# untitled.net
KiCad netlist of a schematic drawn in EAGLE
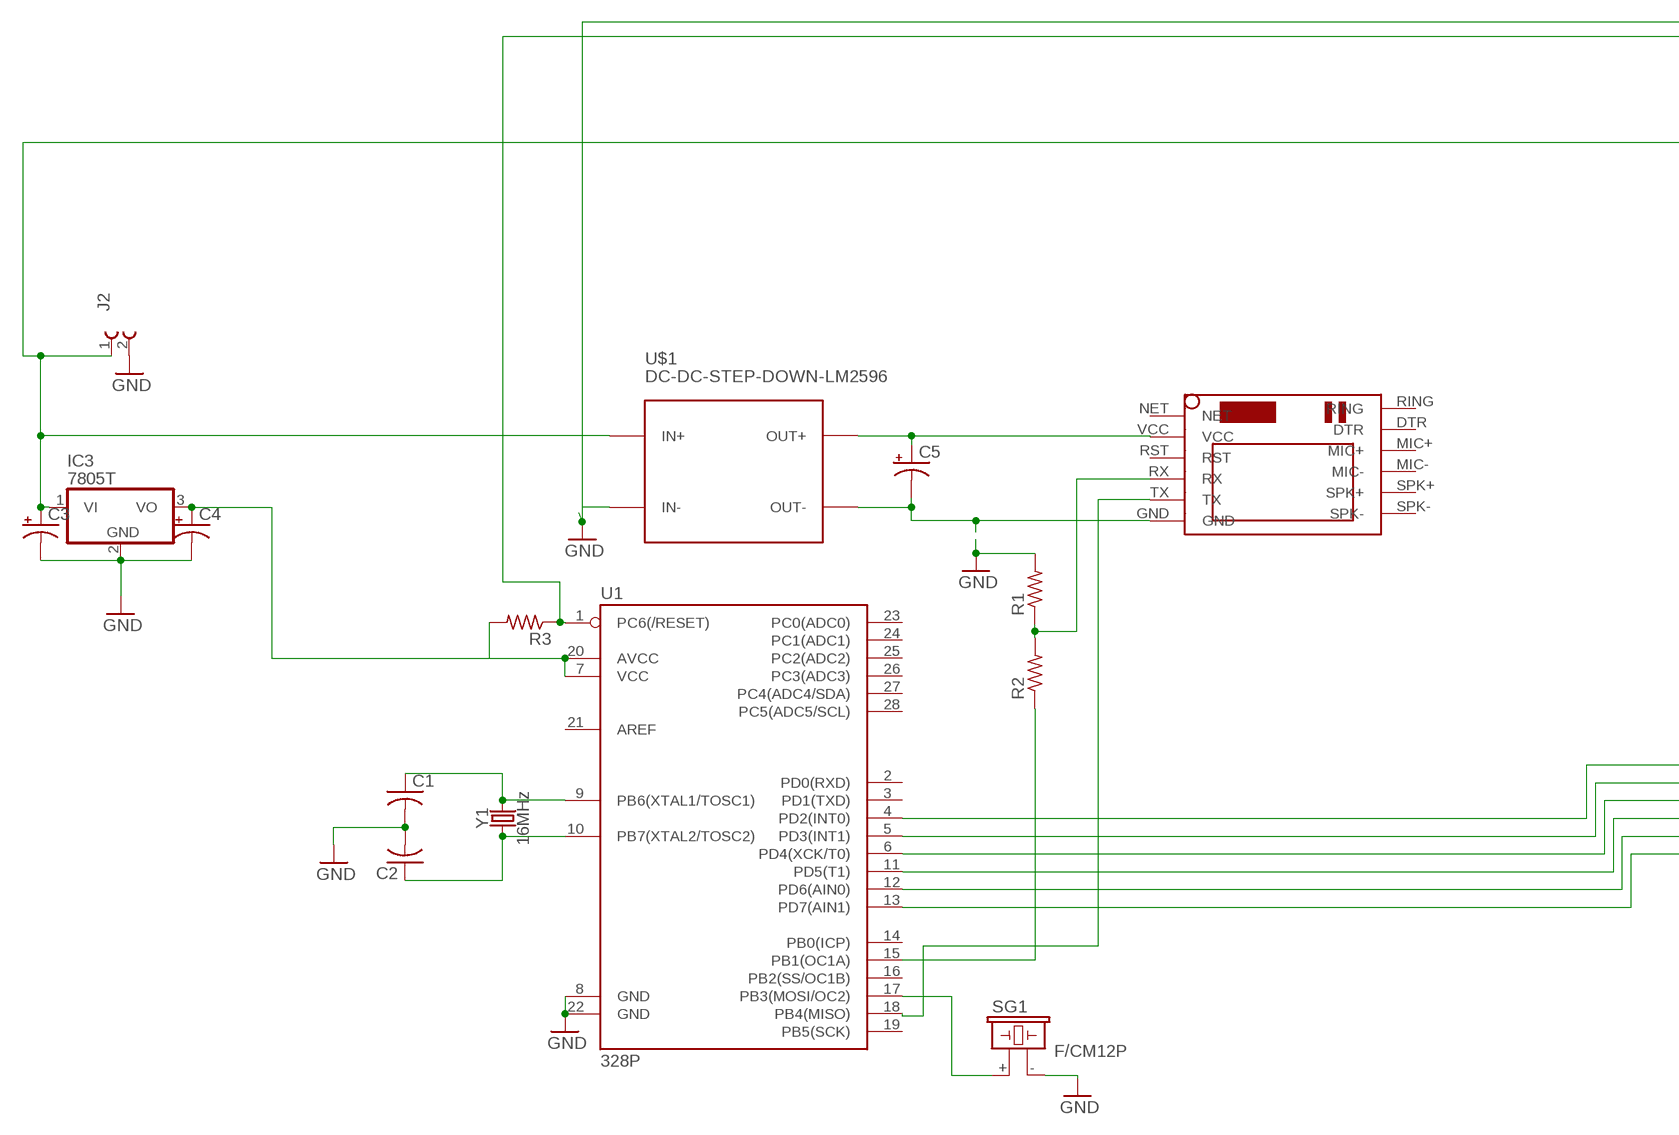
[diagram p0: schematic, sheet 1, part 1 of 2]
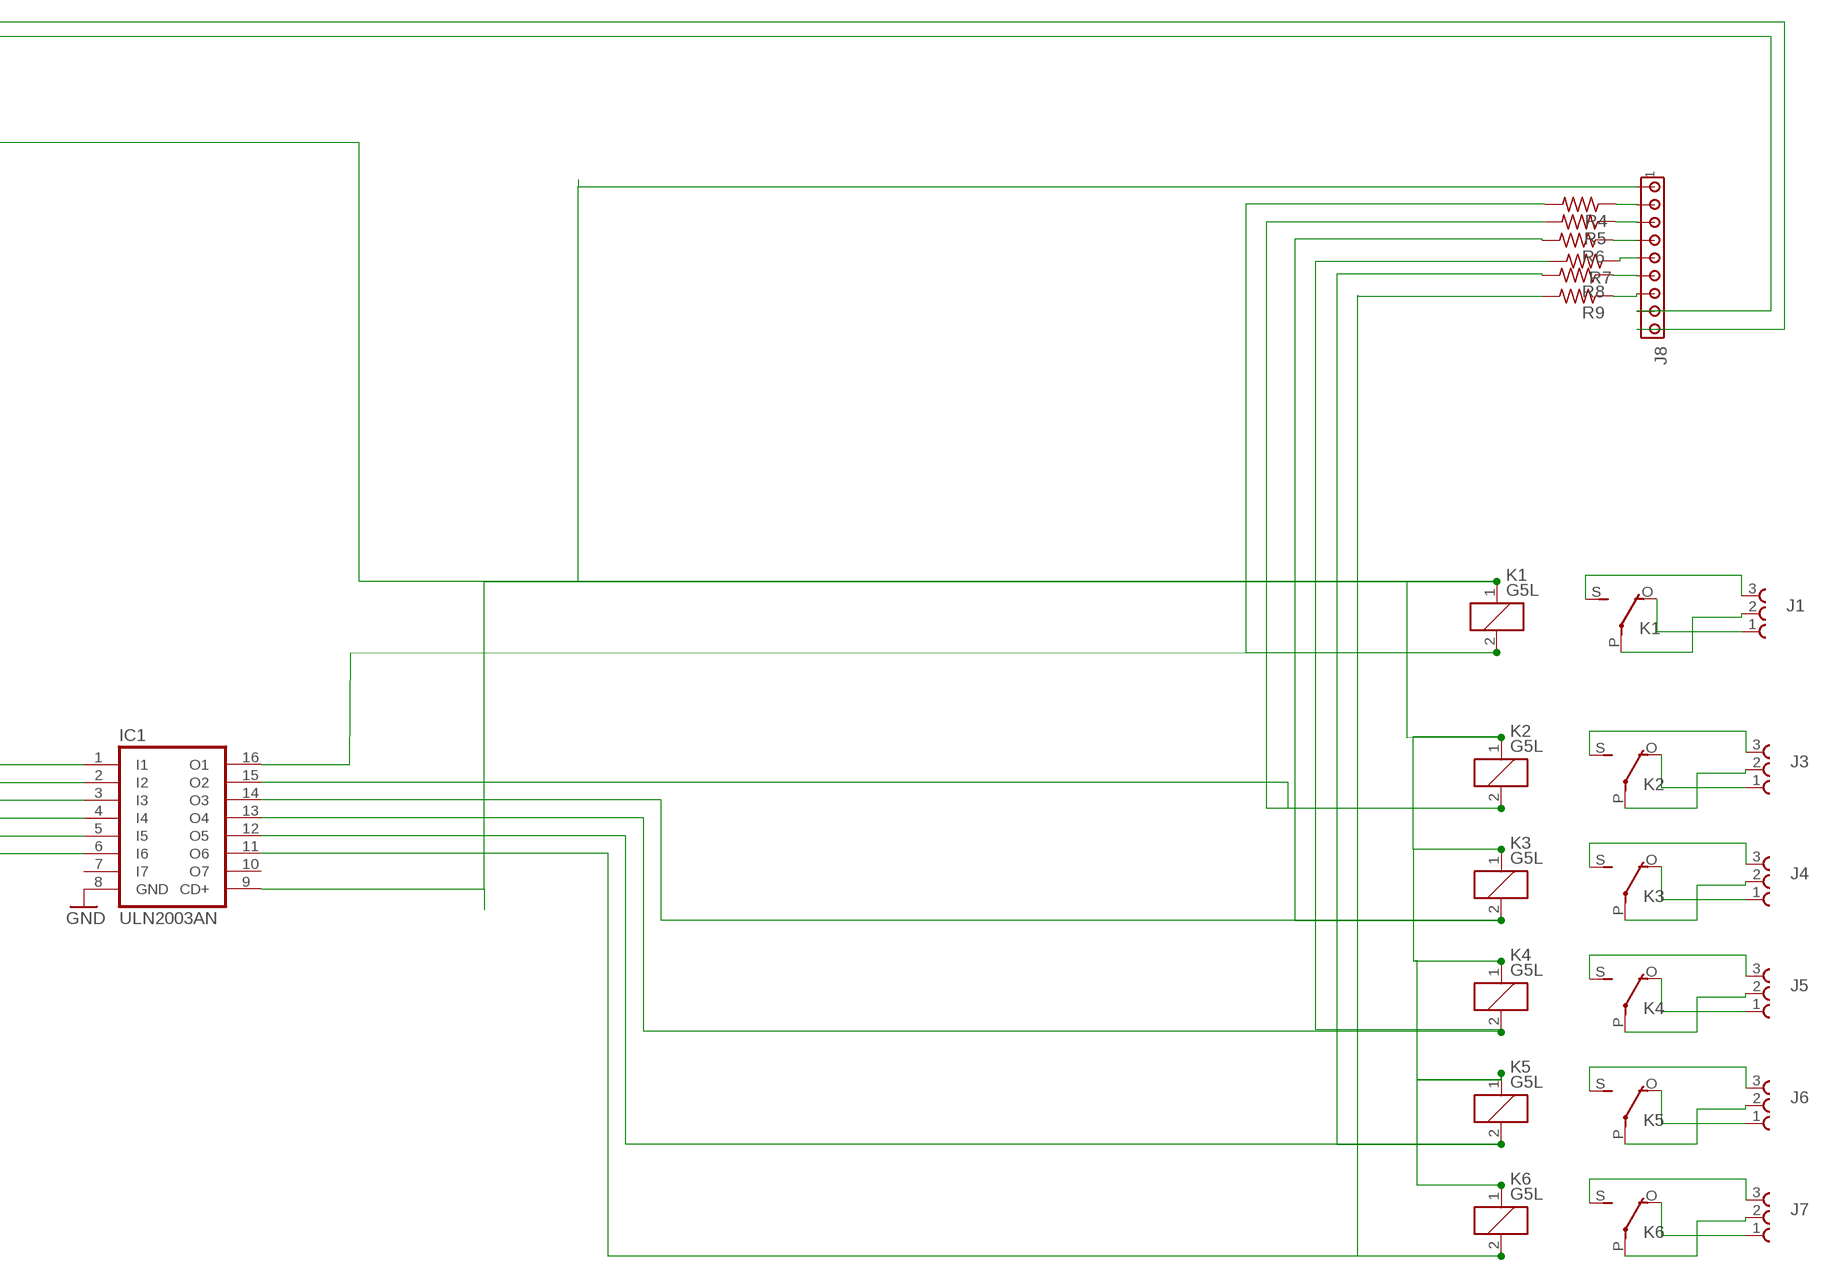
[diagram p1: schematic, sheet 1, part 2 of 2]

(export (version "E")
  (design (tool "Eeschema 10.0.6"))
  (components
    (comp (ref "C1")
      (value "C-US025-024X044")
      (footprint "eagle-import:C025-024X044")
      (libsource (lib "eagle-import") (part "C-US025-024X044"))
    )
    (comp (ref "C2")
      (value "C-US025-024X044")
      (footprint "eagle-import:C025-024X044")
      (libsource (lib "eagle-import") (part "C-US025-024X044"))
    )
    (comp (ref "C3")
      (value "CPOL-USE2.5-5")
      (footprint "eagle-import:E2,5-5")
      (libsource (lib "eagle-import") (part "CPOL-USE2.5-5"))
    )
    (comp (ref "C4")
      (value "CPOL-USE2.5-5")
      (footprint "eagle-import:E2,5-5")
      (libsource (lib "eagle-import") (part "CPOL-USE2.5-5"))
    )
    (comp (ref "C5")
      (value "CAPACITOR-PE5-8.5")
      (footprint "eagle-import:E5-8,5")
      (libsource (lib "eagle-import") (part "CAPACITOR-PE5-8.5"))
    )
    (comp (ref "IC1")
      (value "ULN2003AN")
      (footprint "eagle-import:DIL16")
      (libsource (lib "eagle-import") (part "ULN2003AN"))
    )
    (comp (ref "IC3")
      (value "7805T")
      (footprint "eagle-import:TO220H")
      (libsource (lib "eagle-import") (part "78T05"))
    )
    (comp (ref "J1")
      (value "691216700003")
      (footprint "eagle-import:691216700003")
      (libsource (lib "eagle-import") (part "691216700003"))
    )
    (comp (ref "J2")
      (value "691217910002")
      (footprint "eagle-import:691217910002")
      (libsource (lib "eagle-import") (part "691217910002"))
    )
    (comp (ref "J3")
      (value "691216700003")
      (footprint "eagle-import:691216700003")
      (libsource (lib "eagle-import") (part "691216700003"))
    )
    (comp (ref "J4")
      (value "691216700003")
      (footprint "eagle-import:691216700003")
      (libsource (lib "eagle-import") (part "691216700003"))
    )
    (comp (ref "J5")
      (value "691216700003")
      (footprint "eagle-import:691216700003")
      (libsource (lib "eagle-import") (part "691216700003"))
    )
    (comp (ref "J6")
      (value "691216700003")
      (footprint "eagle-import:691216700003")
      (libsource (lib "eagle-import") (part "691216700003"))
    )
    (comp (ref "J7")
      (value "691216700003")
      (footprint "eagle-import:691216700003")
      (libsource (lib "eagle-import") (part "691216700003"))
    )
    (comp (ref "J8")
      (value "MTA09-100")
      (footprint "eagle-import:10X09MTA")
      (libsource (lib "eagle-import") (part "MTA09-100"))
    )
    (comp (ref "K1")
      (value "G5L")
      (footprint "eagle-import:G5LE")
      (libsource (lib "eagle-import") (part "G5L"))
    )
    (comp (ref "K2")
      (value "G5L")
      (footprint "eagle-import:G5LE")
      (libsource (lib "eagle-import") (part "G5L"))
    )
    (comp (ref "K3")
      (value "G5L")
      (footprint "eagle-import:G5LE")
      (libsource (lib "eagle-import") (part "G5L"))
    )
    (comp (ref "K4")
      (value "G5L")
      (footprint "eagle-import:G5LE")
      (libsource (lib "eagle-import") (part "G5L"))
    )
    (comp (ref "K5")
      (value "G5L")
      (footprint "eagle-import:G5LE")
      (libsource (lib "eagle-import") (part "G5L"))
    )
    (comp (ref "K6")
      (value "G5L")
      (footprint "eagle-import:G5LE")
      (libsource (lib "eagle-import") (part "G5L"))
    )
    (comp (ref "R1")
      (value "R-US_0204/7")
      (footprint "eagle-import:0204_7")
      (libsource (lib "eagle-import") (part "R-US_0204/7"))
    )
    (comp (ref "R2")
      (value "R-US_0204/7")
      (footprint "eagle-import:0204_7")
      (libsource (lib "eagle-import") (part "R-US_0204/7"))
    )
    (comp (ref "R3")
      (value "R-US_0204/7")
      (footprint "eagle-import:0204_7")
      (libsource (lib "eagle-import") (part "R-US_0204/7"))
    )
    (comp (ref "R4")
      (value "R-US_0204/7")
      (footprint "eagle-import:0204_7")
      (libsource (lib "eagle-import") (part "R-US_0204/7"))
    )
    (comp (ref "R5")
      (value "R-US_0204/7")
      (footprint "eagle-import:0204_7")
      (libsource (lib "eagle-import") (part "R-US_0204/7"))
    )
    (comp (ref "R6")
      (value "R-US_0204/7")
      (footprint "eagle-import:0204_7")
      (libsource (lib "eagle-import") (part "R-US_0204/7"))
    )
    (comp (ref "R7")
      (value "R-US_0204/7")
      (footprint "eagle-import:0204_7")
      (libsource (lib "eagle-import") (part "R-US_0204/7"))
    )
    (comp (ref "R8")
      (value "R-US_0204/7")
      (footprint "eagle-import:0204_7")
      (libsource (lib "eagle-import") (part "R-US_0204/7"))
    )
    (comp (ref "R9")
      (value "R-US_0204/7")
      (footprint "eagle-import:0204_7")
      (libsource (lib "eagle-import") (part "R-US_0204/7"))
    )
    (comp (ref "SG1")
      (value "F/CM12P")
      (footprint "eagle-import:F_CM12P")
      (libsource (lib "eagle-import") (part "F/CM12P"))
    )
    (comp (ref "U$1")
      (value "DC-DC-STEP-DOWN-LM2596")
      (footprint "eagle-import:DC-DC-STEP-DOWN-LM2596")
      (libsource (lib "eagle-import") (part "DC-DC-STEP-DOWN-LM2596"))
    )
    (comp (ref "U$2")
      (value "SIM800LMODULE")
      (footprint "eagle-import:SIM800LMODULE")
      (libsource (lib "eagle-import") (part "SIM800LMODULE"))
    )
    (comp (ref "U1")
      (value "328P")
      (footprint "eagle-import:DIP28")
      (libsource (lib "eagle-import") (part "ATMEGA328P_PDIP"))
    )
    (comp (ref "Y1")
      (value "16MHz")
      (footprint "eagle-import:HC49US")
      (libsource (lib "eagle-import") (part "CRYSTAL-16MHZPTH-HC49US"))
    )
  )
  (nets
    (net (code "1") (name "GND") (class "Default")
      (node (ref "C1") (pin "2") (pinfunction "2_2") (pintype "passive"))
      (node (ref "C2") (pin "2") (pinfunction "2_2") (pintype "passive"))
      (node (ref "C3") (pin "-") (pinfunction "-_-") (pintype "passive"))
      (node (ref "C4") (pin "-") (pinfunction "-_-") (pintype "passive"))
      (node (ref "C5") (pin "-") (pinfunction "-_-") (pintype "passive"))
      (node (ref "IC1") (pin "8") (pinfunction "GND_8") (pintype "power_in"))
      (node (ref "IC3") (pin "2") (pinfunction "GND_2") (pintype "passive"))
      (node (ref "J2") (pin "2") (pinfunction "2_2") (pintype "passive"))
      (node (ref "J8") (pin "9") (pinfunction "9_9") (pintype "passive"))
      (node (ref "R1") (pin "2") (pinfunction "2_2") (pintype "passive"))
      (node (ref "SG1") (pin "-") (pinfunction "2_-") (pintype "passive"))
      (node (ref "U$1") (pin "IN-") (pinfunction "IN-_IN-") (pintype "bidirectional"))
      (node (ref "U$1") (pin "OUT-") (pinfunction "OUT-_OUT-") (pintype "bidirectional"))
      (node (ref "U$2") (pin "GND") (pinfunction "GND_GND") (pintype "bidirectional"))
      (node (ref "U1") (pin "22") (pinfunction "GND_22") (pintype "bidirectional"))
      (node (ref "U1") (pin "8") (pinfunction "GND_8") (pintype "bidirectional"))
    )
    (net (code "2") (name "Net-(C5-Pad+)") (class "Default")
      (node (ref "C5") (pin "+") (pinfunction "+_+") (pintype "passive"))
      (node (ref "U$1") (pin "OUT+") (pinfunction "OUT+_OUT+") (pintype "bidirectional"))
      (node (ref "U$2") (pin "VCC") (pinfunction "VCC_VCC") (pintype "bidirectional"))
    )
    (net (code "3") (name "Net-(IC1-CD+)") (class "Default")
      (node (ref "C3") (pin "+") (pinfunction "+_+") (pintype "passive"))
      (node (ref "IC1") (pin "9") (pinfunction "CD+_9") (pintype "passive"))
      (node (ref "IC3") (pin "1") (pinfunction "VI_1") (pintype "input"))
      (node (ref "J2") (pin "1") (pinfunction "1_1") (pintype "passive"))
      (node (ref "J8") (pin "1") (pinfunction "1_1") (pintype "passive"))
      (node (ref "K1") (pin "1") (pinfunction "1_1") (pintype "passive"))
      (node (ref "K2") (pin "1") (pinfunction "1_1") (pintype "passive"))
      (node (ref "K3") (pin "1") (pinfunction "1_1") (pintype "passive"))
      (node (ref "K4") (pin "1") (pinfunction "1_1") (pintype "passive"))
      (node (ref "K5") (pin "1") (pinfunction "1_1") (pintype "passive"))
      (node (ref "K6") (pin "1") (pinfunction "1_1") (pintype "passive"))
      (node (ref "U$1") (pin "IN+") (pinfunction "IN+_IN+") (pintype "bidirectional"))
    )
    (net (code "4") (name "Net-(IC1-I1)") (class "Default")
      (node (ref "IC1") (pin "1") (pinfunction "I1_1") (pintype "input"))
      (node (ref "U1") (pin "4") (pinfunction "PD2(INT0)_4") (pintype "bidirectional"))
    )
    (net (code "5") (name "Net-(IC1-I2)") (class "Default")
      (node (ref "IC1") (pin "2") (pinfunction "I2_2") (pintype "input"))
      (node (ref "U1") (pin "5") (pinfunction "PD3(INT1)_5") (pintype "bidirectional"))
    )
    (net (code "6") (name "Net-(IC1-I3)") (class "Default")
      (node (ref "IC1") (pin "3") (pinfunction "I3_3") (pintype "input"))
      (node (ref "U1") (pin "6") (pinfunction "PD4(XCK/T0)_6") (pintype "bidirectional"))
    )
    (net (code "7") (name "Net-(IC1-I4)") (class "Default")
      (node (ref "IC1") (pin "4") (pinfunction "I4_4") (pintype "input"))
      (node (ref "U1") (pin "11") (pinfunction "PD5(T1)_11") (pintype "bidirectional"))
    )
    (net (code "8") (name "Net-(IC1-I5)") (class "Default")
      (node (ref "IC1") (pin "5") (pinfunction "I5_5") (pintype "input"))
      (node (ref "U1") (pin "12") (pinfunction "PD6(AIN0)_12") (pintype "bidirectional"))
    )
    (net (code "9") (name "Net-(IC1-I6)") (class "Default")
      (node (ref "IC1") (pin "6") (pinfunction "I6_6") (pintype "input"))
      (node (ref "U1") (pin "13") (pinfunction "PD7(AIN1)_13") (pintype "bidirectional"))
    )
    (net (code "10") (name "Net-(IC1-O1)") (class "Default")
      (node (ref "IC1") (pin "16") (pinfunction "O1_16") (pintype "open_collector"))
      (node (ref "K1") (pin "2") (pinfunction "2_2") (pintype "passive"))
      (node (ref "R4") (pin "2") (pinfunction "2_2") (pintype "passive"))
    )
    (net (code "11") (name "Net-(IC1-O2)") (class "Default")
      (node (ref "IC1") (pin "15") (pinfunction "O2_15") (pintype "open_collector"))
      (node (ref "K2") (pin "2") (pinfunction "2_2") (pintype "passive"))
      (node (ref "R5") (pin "2") (pinfunction "2_2") (pintype "passive"))
    )
    (net (code "12") (name "Net-(IC1-O3)") (class "Default")
      (node (ref "IC1") (pin "14") (pinfunction "O3_14") (pintype "open_collector"))
      (node (ref "K3") (pin "2") (pinfunction "2_2") (pintype "passive"))
      (node (ref "R6") (pin "2") (pinfunction "2_2") (pintype "passive"))
    )
    (net (code "13") (name "Net-(IC1-O4)") (class "Default")
      (node (ref "IC1") (pin "13") (pinfunction "O4_13") (pintype "open_collector"))
      (node (ref "K4") (pin "2") (pinfunction "2_2") (pintype "passive"))
      (node (ref "R7") (pin "2") (pinfunction "2_2") (pintype "passive"))
    )
    (net (code "14") (name "Net-(IC1-O5)") (class "Default")
      (node (ref "IC1") (pin "12") (pinfunction "O5_12") (pintype "open_collector"))
      (node (ref "K5") (pin "2") (pinfunction "2_2") (pintype "passive"))
      (node (ref "R8") (pin "2") (pinfunction "2_2") (pintype "passive"))
    )
    (net (code "15") (name "Net-(IC1-O6)") (class "Default")
      (node (ref "IC1") (pin "11") (pinfunction "O6_11") (pintype "open_collector"))
      (node (ref "K6") (pin "2") (pinfunction "2_2") (pintype "passive"))
      (node (ref "R9") (pin "2") (pinfunction "2_2") (pintype "passive"))
    )
    (net (code "16") (name "Net-(IC3-VO)") (class "Default")
      (node (ref "C4") (pin "+") (pinfunction "+_+") (pintype "passive"))
      (node (ref "IC3") (pin "3") (pinfunction "VO_3") (pintype "passive"))
      (node (ref "R3") (pin "2") (pinfunction "2_2") (pintype "passive"))
      (node (ref "U1") (pin "20") (pinfunction "AVCC_20") (pintype "bidirectional"))
      (node (ref "U1") (pin "7") (pinfunction "VCC_7") (pintype "bidirectional"))
    )
    (net (code "17") (name "Net-(J1-1)") (class "Default")
      (node (ref "J1") (pin "3") (pinfunction "1_3") (pintype "passive"))
      (node (ref "K1") (pin "S") (pinfunction "S_S") (pintype "passive"))
    )
    (net (code "18") (name "Net-(J1-3)") (class "Default")
      (node (ref "J1") (pin "1") (pinfunction "3_1") (pintype "passive"))
      (node (ref "K1") (pin "O") (pinfunction "O_O") (pintype "passive"))
    )
    (net (code "19") (name "Net-(J1-Pad2)") (class "Default")
      (node (ref "J1") (pin "2") (pinfunction "2_2") (pintype "passive"))
      (node (ref "K1") (pin "P") (pinfunction "P_P") (pintype "passive"))
    )
    (net (code "20") (name "Net-(J3-1)") (class "Default")
      (node (ref "J3") (pin "3") (pinfunction "1_3") (pintype "passive"))
      (node (ref "K2") (pin "S") (pinfunction "S_S") (pintype "passive"))
    )
    (net (code "21") (name "Net-(J3-3)") (class "Default")
      (node (ref "J3") (pin "1") (pinfunction "3_1") (pintype "passive"))
      (node (ref "K2") (pin "O") (pinfunction "O_O") (pintype "passive"))
    )
    (net (code "22") (name "Net-(J3-Pad2)") (class "Default")
      (node (ref "J3") (pin "2") (pinfunction "2_2") (pintype "passive"))
      (node (ref "K2") (pin "P") (pinfunction "P_P") (pintype "passive"))
    )
    (net (code "23") (name "Net-(J4-1)") (class "Default")
      (node (ref "J4") (pin "3") (pinfunction "1_3") (pintype "passive"))
      (node (ref "K3") (pin "S") (pinfunction "S_S") (pintype "passive"))
    )
    (net (code "24") (name "Net-(J4-3)") (class "Default")
      (node (ref "J4") (pin "1") (pinfunction "3_1") (pintype "passive"))
      (node (ref "K3") (pin "O") (pinfunction "O_O") (pintype "passive"))
    )
    (net (code "25") (name "Net-(J4-Pad2)") (class "Default")
      (node (ref "J4") (pin "2") (pinfunction "2_2") (pintype "passive"))
      (node (ref "K3") (pin "P") (pinfunction "P_P") (pintype "passive"))
    )
    (net (code "26") (name "Net-(J5-1)") (class "Default")
      (node (ref "J5") (pin "3") (pinfunction "1_3") (pintype "passive"))
      (node (ref "K4") (pin "S") (pinfunction "S_S") (pintype "passive"))
    )
    (net (code "27") (name "Net-(J5-3)") (class "Default")
      (node (ref "J5") (pin "1") (pinfunction "3_1") (pintype "passive"))
      (node (ref "K4") (pin "O") (pinfunction "O_O") (pintype "passive"))
    )
    (net (code "28") (name "Net-(J5-Pad2)") (class "Default")
      (node (ref "J5") (pin "2") (pinfunction "2_2") (pintype "passive"))
      (node (ref "K4") (pin "P") (pinfunction "P_P") (pintype "passive"))
    )
    (net (code "29") (name "Net-(J6-1)") (class "Default")
      (node (ref "J6") (pin "3") (pinfunction "1_3") (pintype "passive"))
      (node (ref "K5") (pin "S") (pinfunction "S_S") (pintype "passive"))
    )
    (net (code "30") (name "Net-(J6-3)") (class "Default")
      (node (ref "J6") (pin "1") (pinfunction "3_1") (pintype "passive"))
      (node (ref "K5") (pin "O") (pinfunction "O_O") (pintype "passive"))
    )
    (net (code "31") (name "Net-(J6-Pad2)") (class "Default")
      (node (ref "J6") (pin "2") (pinfunction "2_2") (pintype "passive"))
      (node (ref "K5") (pin "P") (pinfunction "P_P") (pintype "passive"))
    )
    (net (code "32") (name "Net-(J7-1)") (class "Default")
      (node (ref "J7") (pin "3") (pinfunction "1_3") (pintype "passive"))
      (node (ref "K6") (pin "S") (pinfunction "S_S") (pintype "passive"))
    )
    (net (code "33") (name "Net-(J7-3)") (class "Default")
      (node (ref "J7") (pin "1") (pinfunction "3_1") (pintype "passive"))
      (node (ref "K6") (pin "O") (pinfunction "O_O") (pintype "passive"))
    )
    (net (code "34") (name "Net-(J7-Pad2)") (class "Default")
      (node (ref "J7") (pin "2") (pinfunction "2_2") (pintype "passive"))
      (node (ref "K6") (pin "P") (pinfunction "P_P") (pintype "passive"))
    )
    (net (code "35") (name "Net-(J8-Pad2)") (class "Default")
      (node (ref "J8") (pin "2") (pinfunction "2_2") (pintype "passive"))
      (node (ref "R4") (pin "1") (pinfunction "1_1") (pintype "passive"))
    )
    (net (code "36") (name "Net-(J8-Pad3)") (class "Default")
      (node (ref "J8") (pin "3") (pinfunction "3_3") (pintype "passive"))
      (node (ref "R5") (pin "1") (pinfunction "1_1") (pintype "passive"))
    )
    (net (code "37") (name "Net-(J8-Pad4)") (class "Default")
      (node (ref "J8") (pin "4") (pinfunction "4_4") (pintype "passive"))
      (node (ref "R6") (pin "1") (pinfunction "1_1") (pintype "passive"))
    )
    (net (code "38") (name "Net-(J8-Pad5)") (class "Default")
      (node (ref "J8") (pin "5") (pinfunction "5_5") (pintype "passive"))
      (node (ref "R7") (pin "1") (pinfunction "1_1") (pintype "passive"))
    )
    (net (code "39") (name "Net-(J8-Pad6)") (class "Default")
      (node (ref "J8") (pin "6") (pinfunction "6_6") (pintype "passive"))
      (node (ref "R8") (pin "1") (pinfunction "1_1") (pintype "passive"))
    )
    (net (code "40") (name "Net-(J8-Pad7)") (class "Default")
      (node (ref "J8") (pin "7") (pinfunction "7_7") (pintype "passive"))
      (node (ref "R9") (pin "1") (pinfunction "1_1") (pintype "passive"))
    )
    (net (code "41") (name "Net-(R1-Pad1)") (class "Default")
      (node (ref "R1") (pin "1") (pinfunction "1_1") (pintype "passive"))
      (node (ref "R2") (pin "2") (pinfunction "2_2") (pintype "passive"))
      (node (ref "U$2") (pin "RX") (pinfunction "RX_RX") (pintype "bidirectional"))
    )
    (net (code "42") (name "Net-(SG1-1)") (class "Default")
      (node (ref "SG1") (pin "+") (pinfunction "1_+") (pintype "passive"))
      (node (ref "U1") (pin "17") (pinfunction "PB3(MOSI/OC2)_17") (pintype "bidirectional"))
    )
    (net (code "43") (name "Net-(U1-PB1(OC1A))") (class "Default")
      (node (ref "R2") (pin "1") (pinfunction "1_1") (pintype "passive"))
      (node (ref "U1") (pin "15") (pinfunction "PB1(OC1A)_15") (pintype "bidirectional"))
    )
    (net (code "44") (name "Net-(U1-PB4(MISO))") (class "Default")
      (node (ref "U$2") (pin "TX") (pinfunction "TX_TX") (pintype "bidirectional"))
      (node (ref "U1") (pin "18") (pinfunction "PB4(MISO)_18") (pintype "bidirectional"))
    )
    (net (code "45") (name "Net-(U1-PB6(XTAL1{slash}TOSC1))") (class "Default")
      (node (ref "C1") (pin "1") (pinfunction "1_1") (pintype "passive"))
      (node (ref "U1") (pin "9") (pinfunction "PB6(XTAL1/TOSC1)_9") (pintype "bidirectional"))
      (node (ref "Y1") (pin "2") (pinfunction "2_2") (pintype "passive"))
    )
    (net (code "46") (name "Net-(U1-PB7(XTAL2{slash}TOSC2))") (class "Default")
      (node (ref "C2") (pin "1") (pinfunction "1_1") (pintype "passive"))
      (node (ref "U1") (pin "10") (pinfunction "PB7(XTAL2/TOSC2)_10") (pintype "bidirectional"))
      (node (ref "Y1") (pin "1") (pinfunction "1_1") (pintype "passive"))
    )
    (net (code "47") (name "Net-(U1-PC6({slash}RESET))") (class "Default")
      (node (ref "J8") (pin "8") (pinfunction "8_8") (pintype "passive"))
      (node (ref "R3") (pin "1") (pinfunction "1_1") (pintype "passive"))
      (node (ref "U1") (pin "1") (pinfunction "PC6(/RESET)_1") (pintype "bidirectional"))
    )
    (net (code "48") (name "unconnected-(IC1-I7-Pad7)") (class "Default")
      (node (ref "IC1") (pin "7") (pinfunction "I7_7") (pintype "input"))
    )
    (net (code "49") (name "unconnected-(IC1-O7-Pad10)") (class "Default")
      (node (ref "IC1") (pin "10") (pinfunction "O7_10") (pintype "open_collector"))
    )
    (net (code "50") (name "unconnected-(U$2-PadDTR)") (class "Default")
      (node (ref "U$2") (pin "DTR") (pinfunction "DTR_DTR") (pintype "bidirectional"))
    )
    (net (code "51") (name "unconnected-(U$2-PadMIC+)") (class "Default")
      (node (ref "U$2") (pin "MIC+") (pinfunction "MIC+_MIC+") (pintype "bidirectional"))
    )
    (net (code "52") (name "unconnected-(U$2-PadMIC-)") (class "Default")
      (node (ref "U$2") (pin "MIC-") (pinfunction "MIC-_MIC-") (pintype "bidirectional"))
    )
    (net (code "53") (name "unconnected-(U$2-PadNET)") (class "Default")
      (node (ref "U$2") (pin "NET") (pinfunction "NET_NET") (pintype "bidirectional"))
    )
    (net (code "54") (name "unconnected-(U$2-PadRING)") (class "Default")
      (node (ref "U$2") (pin "RING") (pinfunction "RING_RING") (pintype "bidirectional"))
    )
    (net (code "55") (name "unconnected-(U$2-PadRST)") (class "Default")
      (node (ref "U$2") (pin "RST") (pinfunction "RST_RST") (pintype "bidirectional"))
    )
    (net (code "56") (name "unconnected-(U$2-PadSPK+)") (class "Default")
      (node (ref "U$2") (pin "SPK+") (pinfunction "SPK+_SPK+") (pintype "bidirectional"))
    )
    (net (code "57") (name "unconnected-(U$2-PadSPK-)") (class "Default")
      (node (ref "U$2") (pin "SPK-") (pinfunction "SPK-_SPK-") (pintype "bidirectional"))
    )
    (net (code "58") (name "unconnected-(U1-AREF-Pad21)") (class "Default")
      (node (ref "U1") (pin "21") (pinfunction "AREF_21") (pintype "bidirectional"))
    )
    (net (code "59") (name "unconnected-(U1-PB0(ICP)-Pad14)") (class "Default")
      (node (ref "U1") (pin "14") (pinfunction "PB0(ICP)_14") (pintype "bidirectional"))
    )
    (net (code "60") (name "unconnected-(U1-PB2(SS{slash}OC1B)-Pad16)") (class "Default")
      (node (ref "U1") (pin "16") (pinfunction "PB2(SS/OC1B)_16") (pintype "bidirectional"))
    )
    (net (code "61") (name "unconnected-(U1-PB5(SCK)-Pad19)") (class "Default")
      (node (ref "U1") (pin "19") (pinfunction "PB5(SCK)_19") (pintype "bidirectional"))
    )
    (net (code "62") (name "unconnected-(U1-PC0(ADC0)-Pad23)") (class "Default")
      (node (ref "U1") (pin "23") (pinfunction "PC0(ADC0)_23") (pintype "bidirectional"))
    )
    (net (code "63") (name "unconnected-(U1-PC1(ADC1)-Pad24)") (class "Default")
      (node (ref "U1") (pin "24") (pinfunction "PC1(ADC1)_24") (pintype "bidirectional"))
    )
    (net (code "64") (name "unconnected-(U1-PC2(ADC2)-Pad25)") (class "Default")
      (node (ref "U1") (pin "25") (pinfunction "PC2(ADC2)_25") (pintype "bidirectional"))
    )
    (net (code "65") (name "unconnected-(U1-PC3(ADC3)-Pad26)") (class "Default")
      (node (ref "U1") (pin "26") (pinfunction "PC3(ADC3)_26") (pintype "bidirectional"))
    )
    (net (code "66") (name "unconnected-(U1-PC4(ADC4{slash}SDA)-Pad27)") (class "Default")
      (node (ref "U1") (pin "27") (pinfunction "PC4(ADC4/SDA)_27") (pintype "bidirectional"))
    )
    (net (code "67") (name "unconnected-(U1-PC5(ADC5{slash}SCL)-Pad28)") (class "Default")
      (node (ref "U1") (pin "28") (pinfunction "PC5(ADC5/SCL)_28") (pintype "bidirectional"))
    )
    (net (code "68") (name "unconnected-(U1-PD0(RXD)-Pad2)") (class "Default")
      (node (ref "U1") (pin "2") (pinfunction "PD0(RXD)_2") (pintype "bidirectional"))
    )
    (net (code "69") (name "unconnected-(U1-PD1(TXD)-Pad3)") (class "Default")
      (node (ref "U1") (pin "3") (pinfunction "PD1(TXD)_3") (pintype "bidirectional"))
    )
  )
)
